# avip-mod_v4.net
KiCad netlist of a schematic drawn in EAGLE
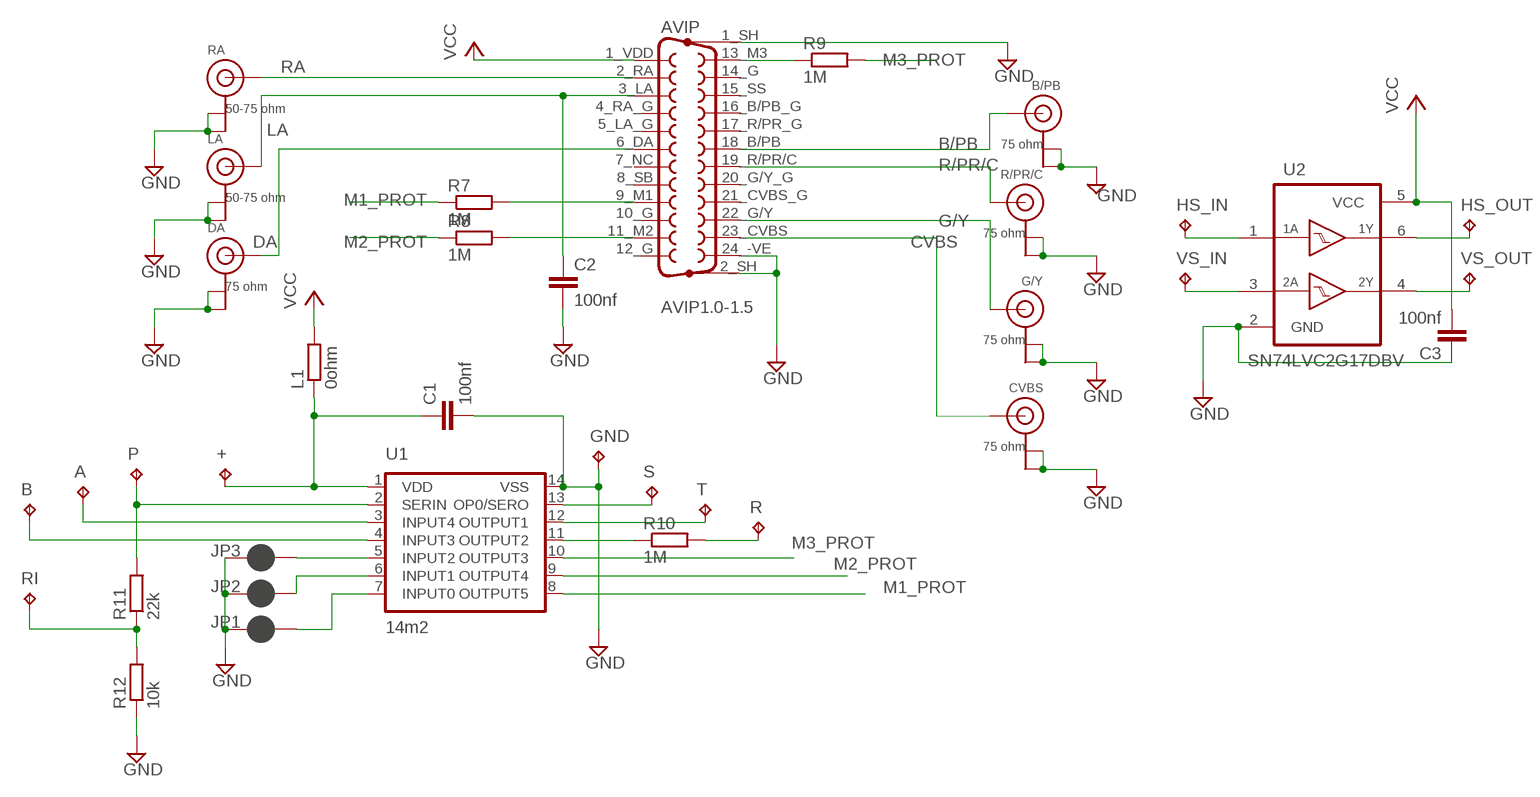
[diagram p0: schematic, sheet 1]

(export (version "E")
  (design (tool "Eeschema 10.0.6"))
  (components
    (comp (ref "+")
      (value "TPTP07SQ")
      (footprint "eagle-import:TP07SQ")
      (libsource (lib "eagle-import") (part "TPTP07SQ"))
    )
    (comp (ref "A")
      (value "TPTP07SQ")
      (footprint "eagle-import:TP07SQ")
      (libsource (lib "eagle-import") (part "TPTP07SQ"))
    )
    (comp (ref "AVIP")
      (value "AVIP1.0-1.5")
      (footprint "eagle-import:AVIP-1.0-1.5")
      (libsource (lib "eagle-import") (part "AVIP1.0-1.5"))
    )
    (comp (ref "B")
      (value "TPTP07SQ")
      (footprint "eagle-import:TP07SQ")
      (libsource (lib "eagle-import") (part "TPTP07SQ"))
    )
    (comp (ref "B/PB")
      (value "75 ohm")
      (footprint "eagle-import:U.FL")
      (libsource (lib "eagle-import") (part "ANTENNA_U.FL"))
    )
    (comp (ref "C1")
      (value "100nf")
      (footprint "eagle-import:C0603")
      (libsource (lib "eagle-import") (part "C-EUC0603"))
    )
    (comp (ref "C2")
      (value "100nf")
      (footprint "eagle-import:C0603")
      (libsource (lib "eagle-import") (part "C-EUC0603"))
    )
    (comp (ref "C3")
      (value "100nf")
      (footprint "eagle-import:C0603")
      (libsource (lib "eagle-import") (part "C-EUC0603"))
    )
    (comp (ref "CVBS")
      (value "75 ohm")
      (footprint "eagle-import:U.FL")
      (libsource (lib "eagle-import") (part "ANTENNA_U.FL"))
    )
    (comp (ref "DA")
      (value "75 ohm")
      (footprint "eagle-import:U.FL")
      (libsource (lib "eagle-import") (part "ANTENNA_U.FL"))
    )
    (comp (ref "G/Y")
      (value "75 ohm")
      (footprint "eagle-import:U.FL")
      (libsource (lib "eagle-import") (part "ANTENNA_U.FL"))
    )
    (comp (ref "GND")
      (value "TPTP07SQ")
      (footprint "eagle-import:TP07SQ")
      (libsource (lib "eagle-import") (part "TPTP07SQ"))
    )
    (comp (ref "HS_IN")
      (value "TPTP07SQ")
      (footprint "eagle-import:TP07SQ")
      (libsource (lib "eagle-import") (part "TPTP07SQ"))
    )
    (comp (ref "HS_OUT")
      (value "TPTP07SQ")
      (footprint "eagle-import:TP07SQ")
      (libsource (lib "eagle-import") (part "TPTP07SQ"))
    )
    (comp (ref "JP1")
      (value "JUMPER-SMT_NO-SILK")
      (footprint "eagle-import:SMT-JUMPER")
      (libsource (lib "eagle-import") (part "JUMPER-SMT_NO-SILK"))
    )
    (comp (ref "JP2")
      (value "JUMPER-SMT_NO-SILK")
      (footprint "eagle-import:SMT-JUMPER")
      (libsource (lib "eagle-import") (part "JUMPER-SMT_NO-SILK"))
    )
    (comp (ref "JP3")
      (value "JUMPER-SMT_NO-SILK")
      (footprint "eagle-import:SMT-JUMPER")
      (libsource (lib "eagle-import") (part "JUMPER-SMT_NO-SILK"))
    )
    (comp (ref "L1")
      (value "0ohm")
      (footprint "eagle-import:R0603")
      (libsource (lib "eagle-import") (part "R-EU_R0603"))
    )
    (comp (ref "LA")
      (value "50-75 ohm")
      (footprint "eagle-import:U.FL")
      (libsource (lib "eagle-import") (part "ANTENNA_U.FL"))
    )
    (comp (ref "P")
      (value "TPTP07SQ")
      (footprint "eagle-import:TP07SQ")
      (libsource (lib "eagle-import") (part "TPTP07SQ"))
    )
    (comp (ref "R")
      (value "TPTP07SQ")
      (footprint "eagle-import:TP07SQ")
      (libsource (lib "eagle-import") (part "TPTP07SQ"))
    )
    (comp (ref "R/PR/C")
      (value "75 ohm")
      (footprint "eagle-import:U.FL")
      (libsource (lib "eagle-import") (part "ANTENNA_U.FL"))
    )
    (comp (ref "R7")
      (value "1M")
      (footprint "eagle-import:R0603")
      (libsource (lib "eagle-import") (part "R-EU_R0603"))
    )
    (comp (ref "R8")
      (value "1M")
      (footprint "eagle-import:R0603")
      (libsource (lib "eagle-import") (part "R-EU_R0603"))
    )
    (comp (ref "R9")
      (value "1M")
      (footprint "eagle-import:R0603")
      (libsource (lib "eagle-import") (part "R-EU_R0603"))
    )
    (comp (ref "R10")
      (value "1M")
      (footprint "eagle-import:R0603")
      (libsource (lib "eagle-import") (part "R-EU_R0603"))
    )
    (comp (ref "R11")
      (value "22k")
      (footprint "eagle-import:R0603")
      (libsource (lib "eagle-import") (part "R-EU_R0603"))
    )
    (comp (ref "R12")
      (value "10k")
      (footprint "eagle-import:R0603")
      (libsource (lib "eagle-import") (part "R-EU_R0603"))
    )
    (comp (ref "RA")
      (value "50-75 ohm")
      (footprint "eagle-import:U.FL")
      (libsource (lib "eagle-import") (part "ANTENNA_U.FL"))
    )
    (comp (ref "RI")
      (value "TPTP07SQ")
      (footprint "eagle-import:TP07SQ")
      (libsource (lib "eagle-import") (part "TPTP07SQ"))
    )
    (comp (ref "S")
      (value "TPTP07SQ")
      (footprint "eagle-import:TP07SQ")
      (libsource (lib "eagle-import") (part "TPTP07SQ"))
    )
    (comp (ref "T")
      (value "TPTP07SQ")
      (footprint "eagle-import:TP07SQ")
      (libsource (lib "eagle-import") (part "TPTP07SQ"))
    )
    (comp (ref "U1")
      (value "14m2")
      (footprint "eagle-import:SO14")
      (libsource (lib "eagle-import") (part "PICAXE-14AXE017M2SM"))
    )
    (comp (ref "U2")
      (value "SN74LVC2G17DBV")
      (footprint "eagle-import:SOT23-6")
      (libsource (lib "eagle-import") (part "SN74LVC2G17DBV"))
    )
    (comp (ref "VS_IN")
      (value "TPTP07SQ")
      (footprint "eagle-import:TP07SQ")
      (libsource (lib "eagle-import") (part "TPTP07SQ"))
    )
    (comp (ref "VS_OUT")
      (value "TPTP07SQ")
      (footprint "eagle-import:TP07SQ")
      (libsource (lib "eagle-import") (part "TPTP07SQ"))
    )
  )
  (nets
    (net (code "1") (name "/B{slash}PB") (class "Default")
      (node (ref "AVIP") (pin "18_B/PB") (pinfunction "18_B/PB_18_B/PB") (pintype "passive"))
      (node (ref "B/PB") (pin "3") (pinfunction "SIGNAL_3") (pintype "passive"))
    )
    (net (code "2") (name "/CVBS") (class "Default")
      (node (ref "AVIP") (pin "23_CVBS") (pinfunction "23_CVBS_23_CVBS") (pintype "passive"))
      (node (ref "CVBS") (pin "3") (pinfunction "SIGNAL_3") (pintype "passive"))
    )
    (net (code "3") (name "/DA") (class "Default")
      (node (ref "AVIP") (pin "6_DA") (pinfunction "6_DA_6_DA") (pintype "passive"))
      (node (ref "DA") (pin "3") (pinfunction "SIGNAL_3") (pintype "passive"))
    )
    (net (code "4") (name "/G{slash}Y") (class "Default")
      (node (ref "AVIP") (pin "22_G/Y") (pinfunction "22_G/Y_22_G/Y") (pintype "passive"))
      (node (ref "G/Y") (pin "3") (pinfunction "SIGNAL_3") (pintype "passive"))
    )
    (net (code "5") (name "/LA") (class "Default")
      (node (ref "AVIP") (pin "3_LA") (pinfunction "3_LA_3_LA") (pintype "passive"))
      (node (ref "C2") (pin "1") (pinfunction "1_1") (pintype "passive"))
      (node (ref "LA") (pin "3") (pinfunction "SIGNAL_3") (pintype "passive"))
    )
    (net (code "6") (name "/M1_PROT") (class "Default")
      (node (ref "R7") (pin "1") (pinfunction "1_1") (pintype "passive"))
      (node (ref "U1") (pin "8") (pinfunction "OUTPUT5_8") (pintype "output"))
    )
    (net (code "7") (name "/M2_PROT") (class "Default")
      (node (ref "R8") (pin "1") (pinfunction "1_1") (pintype "passive"))
      (node (ref "U1") (pin "9") (pinfunction "OUTPUT4_9") (pintype "output"))
    )
    (net (code "8") (name "/M3_PROT") (class "Default")
      (node (ref "R9") (pin "2") (pinfunction "2_2") (pintype "passive"))
      (node (ref "U1") (pin "10") (pinfunction "OUTPUT3_10") (pintype "output"))
    )
    (net (code "9") (name "/RA") (class "Default")
      (node (ref "AVIP") (pin "2_RA") (pinfunction "2_RA_2_RA") (pintype "passive"))
      (node (ref "RA") (pin "3") (pinfunction "SIGNAL_3") (pintype "passive"))
    )
    (net (code "10") (name "/R{slash}PR{slash}C") (class "Default")
      (node (ref "AVIP") (pin "19_R/PR/C") (pinfunction "19_R/PR/C_19_R/PR/C") (pintype "passive"))
      (node (ref "R/PR/C") (pin "3") (pinfunction "SIGNAL_3") (pintype "passive"))
    )
    (net (code "11") (name "GND") (class "Default")
      (node (ref "AVIP") (pin "1_SH") (pinfunction "1_SH_1_SH") (pintype "passive"))
      (node (ref "AVIP") (pin "24_-VE") (pinfunction "25_VSS_24_-VE") (pintype "passive"))
      (node (ref "AVIP") (pin "2_SH") (pinfunction "2_SH_2_SH") (pintype "passive"))
      (node (ref "B/PB") (pin "1") (pinfunction "GND_1") (pintype "passive"))
      (node (ref "B/PB") (pin "2") (pinfunction "GND_2") (pintype "passive"))
      (node (ref "C1") (pin "2") (pinfunction "2_2") (pintype "passive"))
      (node (ref "C2") (pin "2") (pinfunction "2_2") (pintype "passive"))
      (node (ref "C3") (pin "1") (pinfunction "1_1") (pintype "passive"))
      (node (ref "CVBS") (pin "1") (pinfunction "GND_1") (pintype "passive"))
      (node (ref "CVBS") (pin "2") (pinfunction "GND_2") (pintype "passive"))
      (node (ref "DA") (pin "1") (pinfunction "GND_1") (pintype "passive"))
      (node (ref "DA") (pin "2") (pinfunction "GND_2") (pintype "passive"))
      (node (ref "G/Y") (pin "1") (pinfunction "GND_1") (pintype "passive"))
      (node (ref "G/Y") (pin "2") (pinfunction "GND_2") (pintype "passive"))
      (node (ref "GND") (pin "TP") (pinfunction "TP_TP") (pintype "input"))
      (node (ref "JP1") (pin "1") (pinfunction "1_1") (pintype "passive"))
      (node (ref "JP2") (pin "1") (pinfunction "1_1") (pintype "passive"))
      (node (ref "JP3") (pin "1") (pinfunction "1_1") (pintype "passive"))
      (node (ref "LA") (pin "1") (pinfunction "GND_1") (pintype "passive"))
      (node (ref "LA") (pin "2") (pinfunction "GND_2") (pintype "passive"))
      (node (ref "R/PR/C") (pin "1") (pinfunction "GND_1") (pintype "passive"))
      (node (ref "R/PR/C") (pin "2") (pinfunction "GND_2") (pintype "passive"))
      (node (ref "R12") (pin "1") (pinfunction "1_1") (pintype "passive"))
      (node (ref "RA") (pin "1") (pinfunction "GND_1") (pintype "passive"))
      (node (ref "RA") (pin "2") (pinfunction "GND_2") (pintype "passive"))
      (node (ref "U1") (pin "14") (pinfunction "VSS_14") (pintype "power_in"))
      (node (ref "U2") (pin "2") (pinfunction "GND_2") (pintype "power_in"))
    )
    (net (code "12") (name "Net-(AVIP-Pad9_M1)") (class "Default")
      (node (ref "AVIP") (pin "9_M1") (pinfunction "9_M1_9_M1") (pintype "passive"))
      (node (ref "R7") (pin "2") (pinfunction "2_2") (pintype "passive"))
    )
    (net (code "13") (name "Net-(AVIP-Pad11_M2)") (class "Default")
      (node (ref "AVIP") (pin "11_M2") (pinfunction "11_M2_11_M2") (pintype "passive"))
      (node (ref "R8") (pin "2") (pinfunction "2_2") (pintype "passive"))
    )
    (net (code "14") (name "Net-(AVIP-Pad13_M3)") (class "Default")
      (node (ref "AVIP") (pin "13_M3") (pinfunction "13_M3_13_M3") (pintype "passive"))
      (node (ref "R9") (pin "1") (pinfunction "1_1") (pintype "passive"))
    )
    (net (code "15") (name "Net-(R-PadTP)") (class "Default")
      (node (ref "R") (pin "TP") (pinfunction "TP_TP") (pintype "input"))
      (node (ref "R10") (pin "2") (pinfunction "2_2") (pintype "passive"))
    )
    (net (code "16") (name "Net-(R11-Pad1)") (class "Default")
      (node (ref "R11") (pin "1") (pinfunction "1_1") (pintype "passive"))
      (node (ref "R12") (pin "2") (pinfunction "2_2") (pintype "passive"))
      (node (ref "RI") (pin "TP") (pinfunction "TP_TP") (pintype "input"))
    )
    (net (code "17") (name "Net-(U1-INPUT0)") (class "Default")
      (node (ref "JP1") (pin "2") (pinfunction "2_2") (pintype "passive"))
      (node (ref "U1") (pin "7") (pinfunction "INPUT0_7") (pintype "input"))
    )
    (net (code "18") (name "Net-(U1-INPUT1)") (class "Default")
      (node (ref "JP2") (pin "2") (pinfunction "2_2") (pintype "passive"))
      (node (ref "U1") (pin "6") (pinfunction "INPUT1_6") (pintype "input"))
    )
    (net (code "19") (name "Net-(U1-INPUT2)") (class "Default")
      (node (ref "JP3") (pin "2") (pinfunction "2_2") (pintype "passive"))
      (node (ref "U1") (pin "5") (pinfunction "INPUT2_5") (pintype "input"))
    )
    (net (code "20") (name "Net-(U1-INPUT3)") (class "Default")
      (node (ref "B") (pin "TP") (pinfunction "TP_TP") (pintype "input"))
      (node (ref "U1") (pin "4") (pinfunction "INPUT3_4") (pintype "input"))
    )
    (net (code "21") (name "Net-(U1-INPUT4)") (class "Default")
      (node (ref "A") (pin "TP") (pinfunction "TP_TP") (pintype "input"))
      (node (ref "U1") (pin "3") (pinfunction "INPUT4_3") (pintype "input"))
    )
    (net (code "22") (name "Net-(U1-OP0{slash}SERO)") (class "Default")
      (node (ref "S") (pin "TP") (pinfunction "TP_TP") (pintype "input"))
      (node (ref "U1") (pin "13") (pinfunction "OP0/SERO_13") (pintype "output"))
    )
    (net (code "23") (name "Net-(U1-OUTPUT1)") (class "Default")
      (node (ref "T") (pin "TP") (pinfunction "TP_TP") (pintype "input"))
      (node (ref "U1") (pin "12") (pinfunction "OUTPUT1_12") (pintype "output"))
    )
    (net (code "24") (name "Net-(U1-OUTPUT2)") (class "Default")
      (node (ref "R10") (pin "1") (pinfunction "1_1") (pintype "passive"))
      (node (ref "U1") (pin "11") (pinfunction "OUTPUT2_11") (pintype "output"))
    )
    (net (code "25") (name "Net-(U1-SERIN)") (class "Default")
      (node (ref "P") (pin "TP") (pinfunction "TP_TP") (pintype "input"))
      (node (ref "R11") (pin "2") (pinfunction "2_2") (pintype "passive"))
      (node (ref "U1") (pin "2") (pinfunction "SERIN_2") (pintype "input"))
    )
    (net (code "26") (name "Net-(U1-VDD)") (class "Default")
      (node (ref "+") (pin "TP") (pinfunction "TP_TP") (pintype "input"))
      (node (ref "C1") (pin "1") (pinfunction "1_1") (pintype "passive"))
      (node (ref "L1") (pin "1") (pinfunction "1_1") (pintype "passive"))
      (node (ref "U1") (pin "1") (pinfunction "VDD_1") (pintype "power_in"))
    )
    (net (code "27") (name "Net-(U2-1A)") (class "Default")
      (node (ref "HS_IN") (pin "TP") (pinfunction "TP_TP") (pintype "input"))
      (node (ref "U2") (pin "1") (pinfunction "1A_1") (pintype "input"))
    )
    (net (code "28") (name "Net-(U2-1Y)") (class "Default")
      (node (ref "HS_OUT") (pin "TP") (pinfunction "TP_TP") (pintype "input"))
      (node (ref "U2") (pin "6") (pinfunction "1Y_6") (pintype "output"))
    )
    (net (code "29") (name "Net-(U2-2A)") (class "Default")
      (node (ref "U2") (pin "3") (pinfunction "2A_3") (pintype "input"))
      (node (ref "VS_IN") (pin "TP") (pinfunction "TP_TP") (pintype "input"))
    )
    (net (code "30") (name "Net-(U2-2Y)") (class "Default")
      (node (ref "U2") (pin "4") (pinfunction "2Y_4") (pintype "output"))
      (node (ref "VS_OUT") (pin "TP") (pinfunction "TP_TP") (pintype "input"))
    )
    (net (code "31") (name "VCC") (class "Default")
      (node (ref "AVIP") (pin "1_VDD") (pinfunction "1_VDD_1_VDD") (pintype "power_in"))
      (node (ref "C3") (pin "2") (pinfunction "2_2") (pintype "passive"))
      (node (ref "L1") (pin "2") (pinfunction "2_2") (pintype "passive"))
      (node (ref "U2") (pin "5") (pinfunction "VCC_5") (pintype "power_in"))
    )
    (net (code "32") (name "unconnected-(AVIP-Pad4_RA_G)") (class "Default")
      (node (ref "AVIP") (pin "4_RA_G") (pinfunction "4_RA_G_4_RA_G") (pintype "passive"))
    )
    (net (code "33") (name "unconnected-(AVIP-Pad5_LA_G)") (class "Default")
      (node (ref "AVIP") (pin "5_LA_G") (pinfunction "5_LA_G_5_LA_G") (pintype "passive"))
    )
    (net (code "34") (name "unconnected-(AVIP-Pad7_NC)") (class "Default")
      (node (ref "AVIP") (pin "7_NC") (pinfunction "7_NC_7_NC") (pintype "passive"))
    )
    (net (code "35") (name "unconnected-(AVIP-Pad8_SB)") (class "Default")
      (node (ref "AVIP") (pin "8_SB") (pinfunction "8_SB_8_SB") (pintype "passive"))
    )
    (net (code "36") (name "unconnected-(AVIP-Pad10_G)") (class "Default")
      (node (ref "AVIP") (pin "10_G") (pinfunction "10_G_10_G") (pintype "passive"))
    )
    (net (code "37") (name "unconnected-(AVIP-Pad12_G)") (class "Default")
      (node (ref "AVIP") (pin "12_G") (pinfunction "12_G_12_G") (pintype "passive"))
    )
    (net (code "38") (name "unconnected-(AVIP-Pad14_G)") (class "Default")
      (node (ref "AVIP") (pin "14_G") (pinfunction "14_G_14_G") (pintype "passive"))
    )
    (net (code "39") (name "unconnected-(AVIP-Pad15_SS)") (class "Default")
      (node (ref "AVIP") (pin "15_SS") (pinfunction "15_SS_15_SS") (pintype "passive"))
    )
    (net (code "40") (name "unconnected-(AVIP-Pad16_B{slash}PB_G)") (class "Default")
      (node (ref "AVIP") (pin "16_B/PB_G") (pinfunction "16_B/PB_G_16_B/PB_G") (pintype "passive"))
    )
    (net (code "41") (name "unconnected-(AVIP-Pad17_R{slash}PR_G)") (class "Default")
      (node (ref "AVIP") (pin "17_R/PR_G") (pinfunction "17_R/PR_G_17_R/PR_G") (pintype "passive"))
    )
    (net (code "42") (name "unconnected-(AVIP-Pad20_G{slash}Y_G)") (class "Default")
      (node (ref "AVIP") (pin "20_G/Y_G") (pinfunction "20_G/Y_G_20_G/Y_G") (pintype "passive"))
    )
    (net (code "43") (name "unconnected-(AVIP-Pad21_CVBS_G)") (class "Default")
      (node (ref "AVIP") (pin "21_CVBS_G") (pinfunction "21_CVBS_G_21_CVBS_G") (pintype "passive"))
    )
  )
)
